# p2d-001.net
KiCad netlist of a schematic drawn in EAGLE
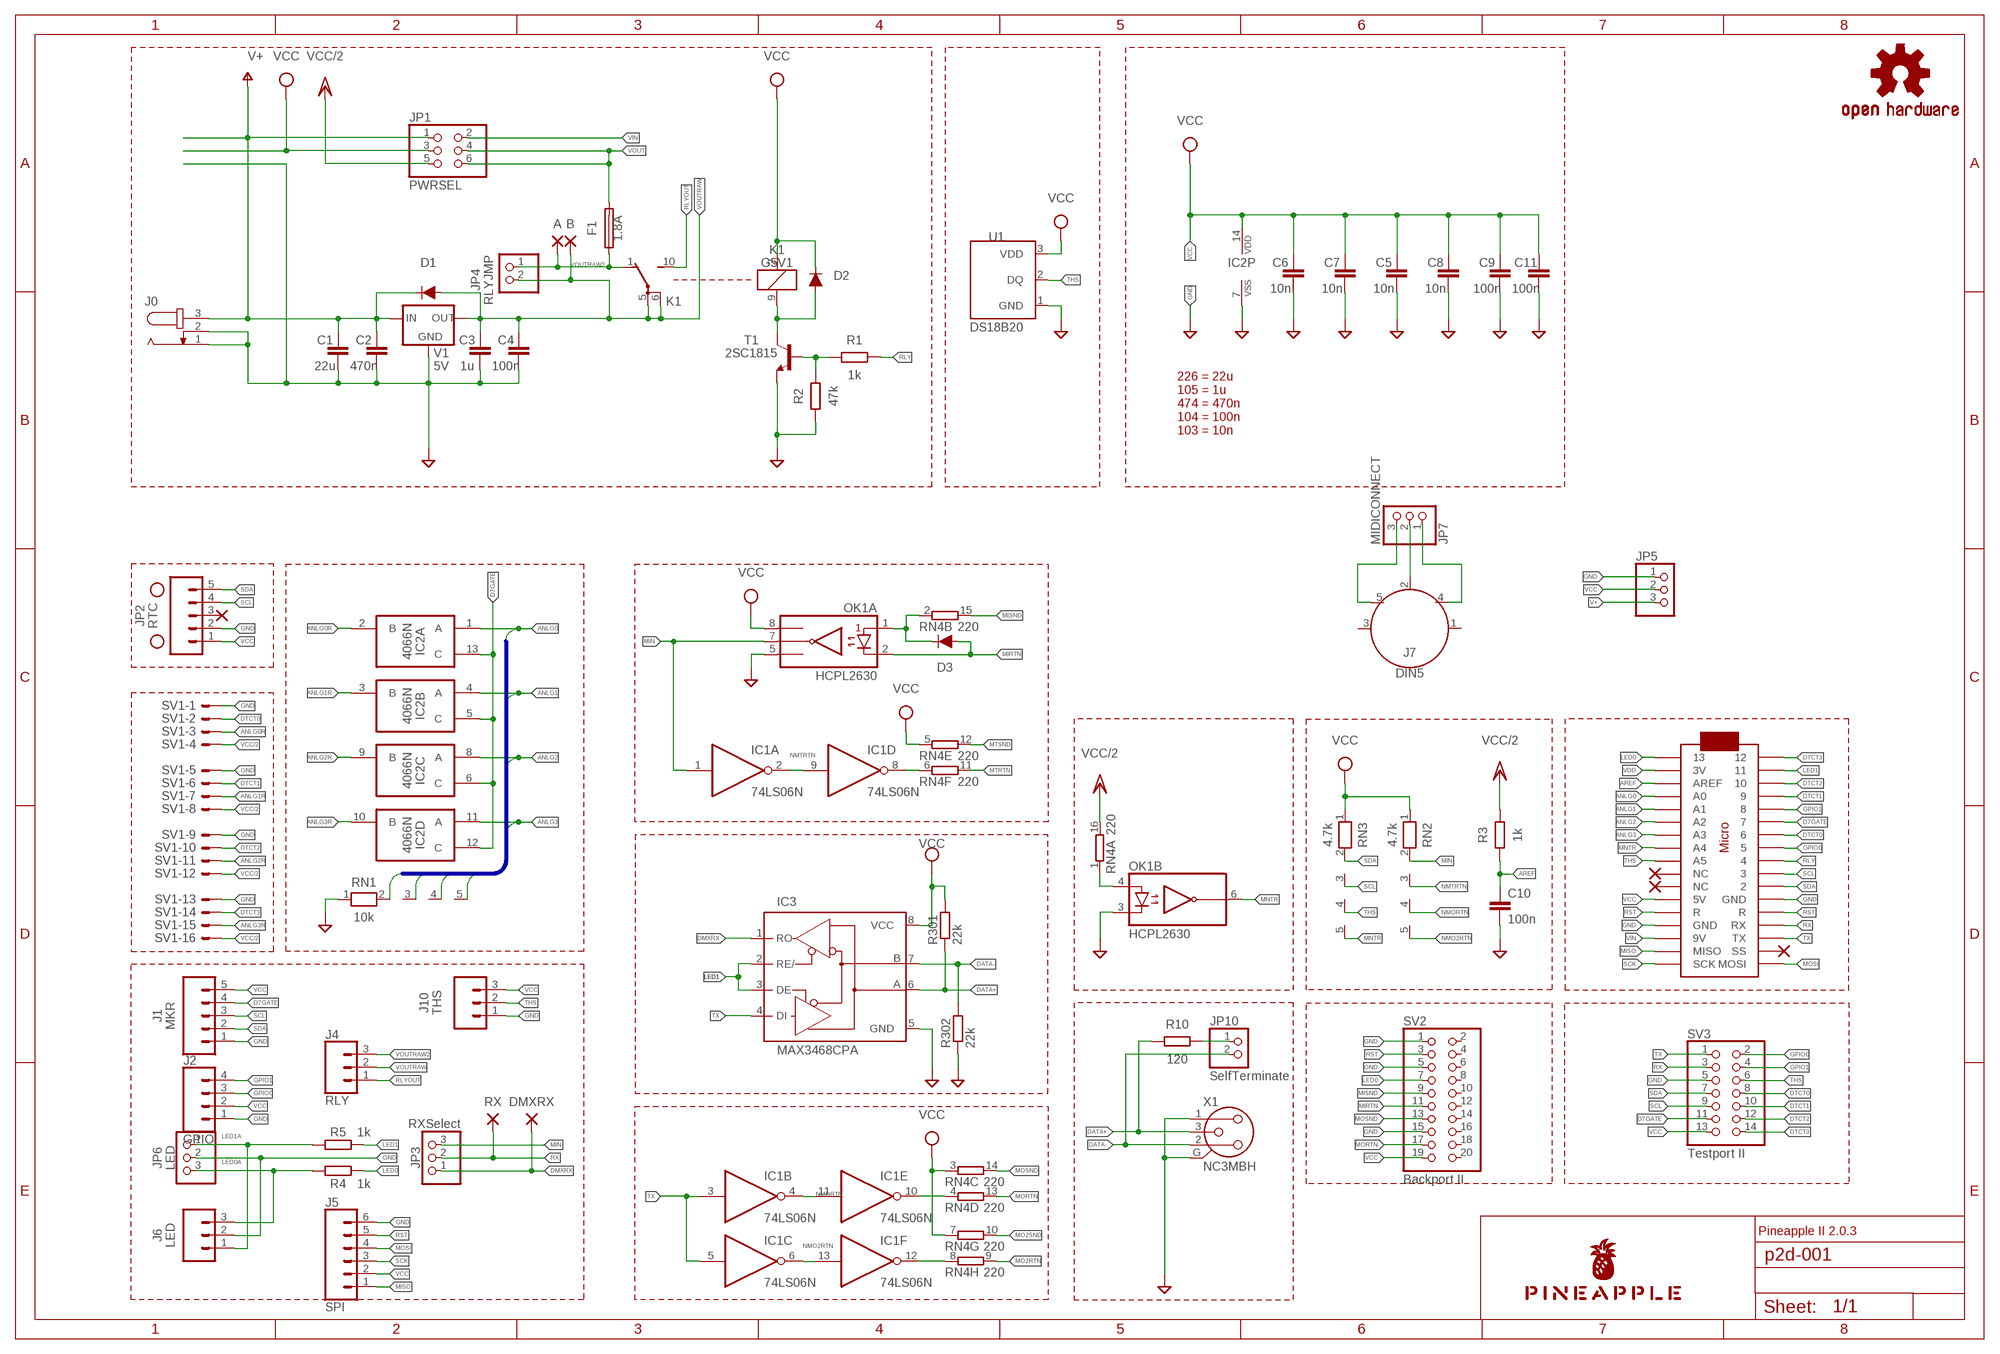
[diagram p0: schematic, sheet 1]

(export (version "E")
  (design (tool "Eeschema 10.0.6"))
  (components
    (comp (ref "A")
      (value "SMD2")
      (footprint "eagle-import:SMD1,27-2,54")
      (libsource (lib "eagle-import") (part "SMD2"))
    )
    (comp (ref "B")
      (value "SMD2")
      (footprint "eagle-import:SMD1,27-2,54")
      (libsource (lib "eagle-import") (part "SMD2"))
    )
    (comp (ref "C1")
      (value "22u")
      (footprint "eagle-import:C025-050X050")
      (libsource (lib "eagle-import") (part "C-EU025-050X050"))
    )
    (comp (ref "C2")
      (value "470n")
      (footprint "eagle-import:C050-024X044")
      (libsource (lib "eagle-import") (part "C-EU050-024X044"))
    )
    (comp (ref "C3")
      (value "1u")
      (footprint "eagle-import:C050-024X044")
      (libsource (lib "eagle-import") (part "C-EU050-024X044"))
    )
    (comp (ref "C4")
      (value "100n")
      (footprint "eagle-import:C025-024X044")
      (libsource (lib "eagle-import") (part "C-EU025-024X044"))
    )
    (comp (ref "C5")
      (value "10n")
      (footprint "eagle-import:C025-024X044")
      (libsource (lib "eagle-import") (part "resistor_348_C-EU025-024X044"))
    )
    (comp (ref "C6")
      (value "10n")
      (footprint "eagle-import:C025-024X044")
      (libsource (lib "eagle-import") (part "resistor_348_C-EU025-024X044"))
    )
    (comp (ref "C7")
      (value "10n")
      (footprint "eagle-import:C025-024X044")
      (libsource (lib "eagle-import") (part "resistor_348_C-EU025-024X044"))
    )
    (comp (ref "C8")
      (value "10n")
      (footprint "eagle-import:C025-024X044")
      (libsource (lib "eagle-import") (part "resistor_348_C-EU025-024X044"))
    )
    (comp (ref "C9")
      (value "100n")
      (footprint "eagle-import:C025-024X044")
      (libsource (lib "eagle-import") (part "resistor_348_C-EU025-024X044"))
    )
    (comp (ref "C10")
      (value "100n")
      (footprint "eagle-import:C025-024X044")
      (libsource (lib "eagle-import") (part "C-EU025-024X044"))
    )
    (comp (ref "C11")
      (value "100n")
      (footprint "eagle-import:C025-024X044")
      (libsource (lib "eagle-import") (part "resistor_348_C-EU025-024X044"))
    )
    (comp (ref "D1")
      (value "DIODE-1N4148")
      (footprint "eagle-import:DIODE-1N4148")
      (libsource (lib "eagle-import") (part "DIODE-1N4148"))
    )
    (comp (ref "D2")
      (value "DIODE-1N4148")
      (footprint "eagle-import:DIODE-1N4148")
      (libsource (lib "eagle-import") (part "DIODE-1N4148"))
    )
    (comp (ref "D3")
      (value "DIODE-1N4148")
      (footprint "eagle-import:DIODE-1N4148")
      (libsource (lib "eagle-import") (part "DIODE-1N4148"))
    )
    (comp (ref "DMXRX")
      (value "SMD2")
      (footprint "eagle-import:SMD1,27-2,54")
      (libsource (lib "eagle-import") (part "SMD2"))
    )
    (comp (ref "F1")
      (value "1.8A")
      (footprint "eagle-import:TE5")
      (libsource (lib "eagle-import") (part "TE5"))
    )
    (comp (ref "H1")
      (value "STAND-OFF")
      (footprint "eagle-import:STAND-OFF")
      (libsource (lib "eagle-import") (part "STAND-OFF"))
    )
    (comp (ref "H2")
      (value "STAND-OFF")
      (footprint "eagle-import:STAND-OFF")
      (libsource (lib "eagle-import") (part "STAND-OFF"))
    )
    (comp (ref "IC1")
      (value "74LS06N")
      (footprint "eagle-import:DIL14")
      (libsource (lib "eagle-import") (part "7406NLS"))
    )
    (comp (ref "IC2")
      (value "4066N")
      (footprint "eagle-import:DIL14")
      (libsource (lib "eagle-import") (part "4066N"))
    )
    (comp (ref "IC3")
      (value "MAX3468CPA")
      (footprint "eagle-import:DIL08")
      (libsource (lib "eagle-import") (part "MAX34PA68C"))
    )
    (comp (ref "J0")
      (value "JACK-PLUG0")
      (footprint "eagle-import:SPC4077")
      (libsource (lib "eagle-import") (part "JACK-PLUG0"))
    )
    (comp (ref "J1")
      (value "MKR")
      (footprint "eagle-import:JST-5-PTH")
      (libsource (lib "eagle-import") (part "CONN_05JST"))
    )
    (comp (ref "J2")
      (value "GPIO")
      (footprint "eagle-import:JST-4-PTH")
      (libsource (lib "eagle-import") (part "CONN_04JST-PTH"))
    )
    (comp (ref "J4")
      (value "RLY")
      (footprint "eagle-import:JST-3-PTH-NS")
      (libsource (lib "eagle-import") (part "CONN_03JST-PTH-NS"))
    )
    (comp (ref "J5")
      (value "SPI")
      (footprint "eagle-import:1X06_1.27MM")
      (libsource (lib "eagle-import") (part "CONN_061.27MM"))
    )
    (comp (ref "J6")
      (value "LED")
      (footprint "eagle-import:JST-3-PTH-VERT")
      (libsource (lib "eagle-import") (part "CONN_03JST-PTH-VERT"))
    )
    (comp (ref "J7")
      (value "DIN5")
      (footprint "eagle-import:DIN5-RA-PTH")
      (libsource (lib "eagle-import") (part "DIN5"))
    )
    (comp (ref "J10")
      (value "THS")
      (footprint "eagle-import:JST-3-PTH")
      (libsource (lib "eagle-import") (part "CONN_03JST-PTH"))
    )
    (comp (ref "JP1")
      (value "PWRSEL")
      (footprint "eagle-import:2X03")
      (libsource (lib "eagle-import") (part "PINHD-2X3"))
    )
    (comp (ref "JP2")
      (value "RTC")
      (footprint "eagle-import:1X05")
      (libsource (lib "eagle-import") (part "CONN_05"))
    )
    (comp (ref "JP3")
      (value "RXSelect")
      (footprint "eagle-import:1X03")
      (libsource (lib "eagle-import") (part "PINHD-1X3"))
    )
    (comp (ref "JP4")
      (value "RLYJMP")
      (footprint "eagle-import:1X02")
      (libsource (lib "eagle-import") (part "PINHD-1X2"))
    )
    (comp (ref "JP5")
      (value "PINHD-1X3")
      (footprint "eagle-import:1X03")
      (libsource (lib "eagle-import") (part "PINHD-1X3"))
    )
    (comp (ref "JP6")
      (value "LED")
      (footprint "eagle-import:1X03")
      (libsource (lib "eagle-import") (part "PINHD-1X3"))
    )
    (comp (ref "JP7")
      (value "MIDICONNECT")
      (footprint "eagle-import:1X03")
      (libsource (lib "eagle-import") (part "PINHD-1X3"))
    )
    (comp (ref "JP10")
      (value "SelfTerminate")
      (footprint "eagle-import:1X02")
      (libsource (lib "eagle-import") (part "PINHD-1X2"))
    )
    (comp (ref "K1")
      (value "G5V1")
      (footprint "eagle-import:G5V1")
      (fields (field (name "MPN") "G5V-1-DC24"))
      (libsource (lib "eagle-import") (part "G5V1"))
    )
    (comp (ref "LOGO1")
      (value "OSHW-LOGOS-COPPER")
      (footprint "eagle-import:OSHW-LOGO-S_COPPER")
      (libsource (lib "eagle-import") (part "OSHW-LOGOS-COPPER"))
    )
    (comp (ref "MC1")
      (value "ARDUINOMICRO")
      (footprint "eagle-import:ARDUINOMICRO")
      (libsource (lib "eagle-import") (part "ARDUINOMICRO"))
    )
    (comp (ref "OK1")
      (value "HCPL2630")
      (footprint "eagle-import:DIL08")
      (fields (field (name "MF") "AGILENT TECHNOLOGIES") (field (name "MPN") "HCPL-2630-000E"))
      (libsource (lib "eagle-import") (part "HCPL2630"))
    )
    (comp (ref "R1")
      (value "1k")
      (footprint "eagle-import:0204_5")
      (libsource (lib "eagle-import") (part "resistor_348_R-EU_0204/5"))
    )
    (comp (ref "R2")
      (value "47k")
      (footprint "eagle-import:0204_5")
      (libsource (lib "eagle-import") (part "resistor_348_R-EU_0204/5"))
    )
    (comp (ref "R3")
      (value "1k")
      (footprint "eagle-import:0204_5")
      (libsource (lib "eagle-import") (part "resistor_348_R-EU_0204/5"))
    )
    (comp (ref "R4")
      (value "1k")
      (footprint "eagle-import:0204_5")
      (libsource (lib "eagle-import") (part "resistor_348_R-EU_0204/5"))
    )
    (comp (ref "R5")
      (value "1k")
      (footprint "eagle-import:0204_5")
      (libsource (lib "eagle-import") (part "resistor_348_R-EU_0204/5"))
    )
    (comp (ref "R10")
      (value "120")
      (footprint "eagle-import:0204_5")
      (libsource (lib "eagle-import") (part "resistor_348_R-EU_0204/5"))
    )
    (comp (ref "R301")
      (value "22k")
      (footprint "eagle-import:M2012")
      (libsource (lib "eagle-import") (part "R-EU_M2012"))
    )
    (comp (ref "R302")
      (value "22k")
      (footprint "eagle-import:M2012")
      (libsource (lib "eagle-import") (part "R-EU_M2012"))
    )
    (comp (ref "RN1")
      (value "10k")
      (footprint "eagle-import:RN-5")
      (libsource (lib "eagle-import") (part "RN04"))
    )
    (comp (ref "RN2")
      (value "4.7k")
      (footprint "eagle-import:RN-5")
      (libsource (lib "eagle-import") (part "RN04"))
    )
    (comp (ref "RN3")
      (value "4.7k")
      (footprint "eagle-import:RN-5")
      (libsource (lib "eagle-import") (part "RN04"))
    )
    (comp (ref "RN4")
      (value "220")
      (footprint "eagle-import:DIL16")
      (libsource (lib "eagle-import") (part "8R-N"))
    )
    (comp (ref "RX")
      (value "SMD2")
      (footprint "eagle-import:SMD1,27-2,54")
      (libsource (lib "eagle-import") (part "SMD2"))
    )
    (comp (ref "SV1")
      (value "ML16LE")
      (footprint "eagle-import:ML16L")
      (libsource (lib "eagle-import") (part "ML16LE"))
    )
    (comp (ref "SV2")
      (value "Backport II")
      (footprint "eagle-import:2X10")
      (libsource (lib "eagle-import") (part "PINHD-2X10"))
    )
    (comp (ref "SV3")
      (value "Testport II")
      (footprint "eagle-import:2X07")
      (libsource (lib "eagle-import") (part "PINHD-2X7"))
    )
    (comp (ref "T1")
      (value "2SC1815")
      (footprint "eagle-import:TO92-ECB")
      (libsource (lib "eagle-import") (part "2SC1815"))
    )
    (comp (ref "U$1")
      (value "PINEAPPLE450_SILK")
      (footprint "eagle-import:PINEAPPLE450_SILK")
      (libsource (lib "eagle-import") (part "PINEAPPLE450_SILK"))
    )
    (comp (ref "U1")
      (value "DS18B20")
      (footprint "eagle-import:TO-92-AMMO")
      (libsource (lib "eagle-import") (part "DS18B20"))
    )
    (comp (ref "V1")
      (value "5V")
      (footprint "eagle-import:78XXL")
      (libsource (lib "eagle-import") (part "78XXL"))
    )
    (comp (ref "X1")
      (value "NC3MBH")
      (footprint "eagle-import:NC3MBH")
      (fields (field (name "MF") "NEUTRIK"))
      (libsource (lib "eagle-import") (part "NC3MBH"))
    )
  )
  (nets
    (net (code "1") (name "/LED0A") (class "Default")
      (node (ref "J6") (pin "3") (pinfunction "3_3") (pintype "passive"))
      (node (ref "JP6") (pin "3") (pinfunction "3_3") (pintype "passive"))
      (node (ref "R4") (pin "1") (pinfunction "1_1") (pintype "passive"))
    )
    (net (code "2") (name "/LED1A") (class "Default")
      (node (ref "J6") (pin "1") (pinfunction "1_1") (pintype "passive"))
      (node (ref "JP6") (pin "1") (pinfunction "1_1") (pintype "passive"))
      (node (ref "R5") (pin "1") (pinfunction "1_1") (pintype "passive"))
    )
    (net (code "3") (name "ANLG0") (class "Default")
      (node (ref "IC2") (pin "1") (pinfunction "A_1") (pintype "tri_state"))
      (node (ref "MC1") (pin "P$31") (pinfunction "A0_P$31") (pintype "bidirectional"))
      (node (ref "RN1") (pin "2") (pinfunction "2_2") (pintype "passive"))
    )
    (net (code "4") (name "ANLG0R") (class "Default")
      (node (ref "IC2") (pin "2") (pinfunction "B_2") (pintype "tri_state"))
      (node (ref "SV1") (pin "3") (pinfunction "S_3") (pintype "passive"))
    )
    (net (code "5") (name "ANLG1") (class "Default")
      (node (ref "IC2") (pin "4") (pinfunction "A_4") (pintype "tri_state"))
      (node (ref "MC1") (pin "P$30") (pinfunction "A1_P$30") (pintype "bidirectional"))
      (node (ref "RN1") (pin "3") (pinfunction "3_3") (pintype "passive"))
    )
    (net (code "6") (name "ANLG1R") (class "Default")
      (node (ref "IC2") (pin "3") (pinfunction "B_3") (pintype "tri_state"))
      (node (ref "SV1") (pin "7") (pinfunction "S_7") (pintype "passive"))
    )
    (net (code "7") (name "ANLG2") (class "Default")
      (node (ref "IC2") (pin "8") (pinfunction "A_8") (pintype "tri_state"))
      (node (ref "MC1") (pin "P$29") (pinfunction "A2_P$29") (pintype "bidirectional"))
      (node (ref "RN1") (pin "4") (pinfunction "4_4") (pintype "passive"))
    )
    (net (code "8") (name "ANLG2R") (class "Default")
      (node (ref "IC2") (pin "9") (pinfunction "B_9") (pintype "tri_state"))
      (node (ref "SV1") (pin "11") (pinfunction "S_11") (pintype "passive"))
    )
    (net (code "9") (name "ANLG3") (class "Default")
      (node (ref "IC2") (pin "11") (pinfunction "A_11") (pintype "tri_state"))
      (node (ref "MC1") (pin "P$28") (pinfunction "A3_P$28") (pintype "bidirectional"))
      (node (ref "RN1") (pin "5") (pinfunction "5_5") (pintype "passive"))
    )
    (net (code "10") (name "ANLG3R") (class "Default")
      (node (ref "IC2") (pin "10") (pinfunction "B_10") (pintype "tri_state"))
      (node (ref "SV1") (pin "15") (pinfunction "S_15") (pintype "passive"))
    )
    (net (code "11") (name "AREF") (class "Default")
      (node (ref "C10") (pin "1") (pinfunction "1_1") (pintype "passive"))
      (node (ref "MC1") (pin "P$32") (pinfunction "AREF_P$32") (pintype "bidirectional"))
      (node (ref "R3") (pin "1") (pinfunction "1_1") (pintype "passive"))
    )
    (net (code "12") (name "D7GATE") (class "Default")
      (node (ref "IC2") (pin "12") (pinfunction "C_12") (pintype "input"))
      (node (ref "IC2") (pin "13") (pinfunction "C_13") (pintype "input"))
      (node (ref "IC2") (pin "5") (pinfunction "C_5") (pintype "input"))
      (node (ref "IC2") (pin "6") (pinfunction "C_6") (pintype "input"))
      (node (ref "J1") (pin "4") (pinfunction "4_4") (pintype "passive"))
      (node (ref "MC1") (pin "P$6") (pinfunction "7_P$6") (pintype "bidirectional"))
      (node (ref "SV3") (pin "11") (pinfunction "11_11") (pintype "passive"))
    )
    (net (code "13") (name "DATA+") (class "Default")
      (node (ref "IC3") (pin "6") (pinfunction "A_6") (pintype "passive"))
      (node (ref "R10") (pin "1") (pinfunction "1_1") (pintype "passive"))
      (node (ref "R301") (pin "1") (pinfunction "1_1") (pintype "passive"))
      (node (ref "X1") (pin "3") (pinfunction "3_3") (pintype "passive"))
    )
    (net (code "14") (name "DATA-") (class "Default")
      (node (ref "IC3") (pin "7") (pinfunction "B_7") (pintype "passive"))
      (node (ref "JP10") (pin "2") (pinfunction "2_2") (pintype "passive"))
      (node (ref "R302") (pin "2") (pinfunction "2_2") (pintype "passive"))
      (node (ref "X1") (pin "2") (pinfunction "2_2") (pintype "passive"))
    )
    (net (code "15") (name "DMXRX") (class "Default")
      (node (ref "DMXRX") (pin "1") (pinfunction "P_1") (pintype "passive"))
      (node (ref "IC3") (pin "1") (pinfunction "RO_1") (pintype "output"))
      (node (ref "JP3") (pin "1") (pinfunction "1_1") (pintype "passive"))
    )
    (net (code "16") (name "DTCT0") (class "Default")
      (node (ref "MC1") (pin "P$7") (pinfunction "6_P$7") (pintype "bidirectional"))
      (node (ref "SV1") (pin "2") (pinfunction "S_2") (pintype "passive"))
      (node (ref "SV3") (pin "8") (pinfunction "8_8") (pintype "passive"))
    )
    (net (code "17") (name "DTCT1") (class "Default")
      (node (ref "MC1") (pin "P$4") (pinfunction "9_P$4") (pintype "bidirectional"))
      (node (ref "SV1") (pin "6") (pinfunction "S_6") (pintype "passive"))
      (node (ref "SV3") (pin "10") (pinfunction "10_10") (pintype "passive"))
    )
    (net (code "18") (name "DTCT2") (class "Default")
      (node (ref "MC1") (pin "P$3") (pinfunction "10_P$3") (pintype "bidirectional"))
      (node (ref "SV1") (pin "10") (pinfunction "S_10") (pintype "passive"))
      (node (ref "SV3") (pin "12") (pinfunction "12_12") (pintype "passive"))
    )
    (net (code "19") (name "DTCT3") (class "Default")
      (node (ref "MC1") (pin "P$1") (pinfunction "12_P$1") (pintype "bidirectional"))
      (node (ref "SV1") (pin "14") (pinfunction "S_14") (pintype "passive"))
      (node (ref "SV3") (pin "14") (pinfunction "14_14") (pintype "passive"))
    )
    (net (code "20") (name "GND") (class "Default")
      (node (ref "C1") (pin "2") (pinfunction "2_2") (pintype "passive"))
      (node (ref "C10") (pin "2") (pinfunction "2_2") (pintype "passive"))
      (node (ref "C11") (pin "2") (pinfunction "2_2") (pintype "passive"))
      (node (ref "C2") (pin "2") (pinfunction "2_2") (pintype "passive"))
      (node (ref "C3") (pin "2") (pinfunction "2_2") (pintype "passive"))
      (node (ref "C4") (pin "2") (pinfunction "2_2") (pintype "passive"))
      (node (ref "C5") (pin "2") (pinfunction "2_2") (pintype "passive"))
      (node (ref "C6") (pin "2") (pinfunction "2_2") (pintype "passive"))
      (node (ref "C7") (pin "2") (pinfunction "2_2") (pintype "passive"))
      (node (ref "C8") (pin "2") (pinfunction "2_2") (pintype "passive"))
      (node (ref "C9") (pin "2") (pinfunction "2_2") (pintype "passive"))
      (node (ref "IC2") (pin "7") (pinfunction "VSS_7") (pintype "power_in"))
      (node (ref "IC3") (pin "5") (pinfunction "GND_5") (pintype "power_in"))
      (node (ref "J0") (pin "1") (pinfunction "1_1") (pintype "passive"))
      (node (ref "J0") (pin "2") (pinfunction "2_2") (pintype "passive"))
      (node (ref "J1") (pin "1") (pinfunction "1_1") (pintype "passive"))
      (node (ref "J10") (pin "1") (pinfunction "1_1") (pintype "passive"))
      (node (ref "J2") (pin "1") (pinfunction "1_1") (pintype "passive"))
      (node (ref "J5") (pin "6") (pinfunction "6_6") (pintype "passive"))
      (node (ref "J6") (pin "2") (pinfunction "2_2") (pintype "passive"))
      (node (ref "JP2") (pin "2") (pinfunction "2_2") (pintype "passive"))
      (node (ref "JP5") (pin "1") (pinfunction "1_1") (pintype "passive"))
      (node (ref "JP6") (pin "2") (pinfunction "2_2") (pintype "passive"))
      (node (ref "MC1") (pin "P$12") (pinfunction "GND_P$12") (pintype "bidirectional"))
      (node (ref "MC1") (pin "P$21") (pinfunction "GND_P$21") (pintype "bidirectional"))
      (node (ref "OK1") (pin "3") (pinfunction "C2_3") (pintype "passive"))
      (node (ref "OK1") (pin "5") (pinfunction "GND_5") (pintype "passive"))
      (node (ref "R2") (pin "1") (pinfunction "1_1") (pintype "passive"))
      (node (ref "R302") (pin "1") (pinfunction "1_1") (pintype "passive"))
      (node (ref "RN1") (pin "1") (pinfunction "1_1") (pintype "passive"))
      (node (ref "SV1") (pin "1") (pinfunction "S_1") (pintype "passive"))
      (node (ref "SV1") (pin "13") (pinfunction "S_13") (pintype "passive"))
      (node (ref "SV1") (pin "5") (pinfunction "S_5") (pintype "passive"))
      (node (ref "SV1") (pin "9") (pinfunction "S_9") (pintype "passive"))
      (node (ref "SV2") (pin "1") (pinfunction "1_1") (pintype "passive"))
      (node (ref "SV2") (pin "15") (pinfunction "15_15") (pintype "passive"))
      (node (ref "SV2") (pin "5") (pinfunction "5_5") (pintype "passive"))
      (node (ref "SV3") (pin "5") (pinfunction "5_5") (pintype "passive"))
      (node (ref "T1") (pin "E") (pinfunction "E_E") (pintype "passive"))
      (node (ref "U1") (pin "1") (pinfunction "GND_1") (pintype "power_in"))
      (node (ref "V1") (pin "GND") (pinfunction "GND_GND") (pintype "input"))
      (node (ref "X1") (pin "1") (pinfunction "1_1") (pintype "passive"))
      (node (ref "X1") (pin "G") (pinfunction "G_G") (pintype "passive"))
    )
    (net (code "21") (name "GPIO0") (class "Default")
      (node (ref "J2") (pin "3") (pinfunction "3_3") (pintype "passive"))
      (node (ref "MC1") (pin "P$8") (pinfunction "5_P$8") (pintype "bidirectional"))
      (node (ref "SV3") (pin "2") (pinfunction "2_2") (pintype "passive"))
    )
    (net (code "22") (name "GPIO1") (class "Default")
      (node (ref "J2") (pin "4") (pinfunction "4_4") (pintype "passive"))
      (node (ref "MC1") (pin "P$5") (pinfunction "8_P$5") (pintype "bidirectional"))
      (node (ref "SV3") (pin "4") (pinfunction "4_4") (pintype "passive"))
    )
    (net (code "23") (name "LED0") (class "Default")
      (node (ref "MC1") (pin "P$34") (pinfunction "13_P$34") (pintype "bidirectional"))
      (node (ref "R4") (pin "2") (pinfunction "2_2") (pintype "passive"))
      (node (ref "SV2") (pin "7") (pinfunction "7_7") (pintype "passive"))
    )
    (net (code "24") (name "LED1") (class "Default")
      (node (ref "IC3") (pin "2") (pinfunction "RE/_2") (pintype "input"))
      (node (ref "IC3") (pin "3") (pinfunction "DE_3") (pintype "input"))
      (node (ref "MC1") (pin "P$2") (pinfunction "11_P$2") (pintype "bidirectional"))
      (node (ref "R5") (pin "2") (pinfunction "2_2") (pintype "passive"))
    )
    (net (code "25") (name "MIN") (class "Default")
      (node (ref "IC1") (pin "1") (pinfunction "I_1") (pintype "input"))
      (node (ref "JP3") (pin "3") (pinfunction "3_3") (pintype "passive"))
      (node (ref "OK1") (pin "7") (pinfunction "VO1_7") (pintype "passive"))
      (node (ref "RN2") (pin "2") (pinfunction "2_2") (pintype "passive"))
    )
    (net (code "26") (name "MIRTN") (class "Default")
      (node (ref "D3") (pin "A") (pinfunction "A_A") (pintype "passive"))
      (node (ref "OK1") (pin "2") (pinfunction "C1_2") (pintype "passive"))
      (node (ref "SV2") (pin "11") (pinfunction "11_11") (pintype "passive"))
    )
    (net (code "27") (name "MISND") (class "Default")
      (node (ref "RN4") (pin "15") (pinfunction "2_15") (pintype "passive"))
      (node (ref "SV2") (pin "9") (pinfunction "9_9") (pintype "passive"))
    )
    (net (code "28") (name "MISO") (class "Default")
      (node (ref "J5") (pin "1") (pinfunction "1_1") (pintype "passive"))
      (node (ref "MC1") (pin "P$19") (pinfunction "MISO_P$19") (pintype "bidirectional"))
    )
    (net (code "29") (name "MNTR") (class "Default")
      (node (ref "MC1") (pin "P$27") (pinfunction "A4_P$27") (pintype "bidirectional"))
      (node (ref "OK1") (pin "6") (pinfunction "VO2_6") (pintype "passive"))
      (node (ref "RN3") (pin "5") (pinfunction "5_5") (pintype "passive"))
    )
    (net (code "30") (name "MO2RTN") (class "Default")
      (node (ref "RN4") (pin "9") (pinfunction "2_9") (pintype "passive"))
    )
    (net (code "31") (name "MO2SND") (class "Default")
      (node (ref "RN4") (pin "10") (pinfunction "2_10") (pintype "passive"))
    )
    (net (code "32") (name "MORTN") (class "Default")
      (node (ref "RN4") (pin "13") (pinfunction "2_13") (pintype "passive"))
      (node (ref "SV2") (pin "17") (pinfunction "17_17") (pintype "passive"))
    )
    (net (code "33") (name "MOSI") (class "Default")
      (node (ref "J5") (pin "4") (pinfunction "4_4") (pintype "passive"))
      (node (ref "MC1") (pin "P$17") (pinfunction "MOSI_P$17") (pintype "bidirectional"))
    )
    (net (code "34") (name "MOSND") (class "Default")
      (node (ref "RN4") (pin "14") (pinfunction "2_14") (pintype "passive"))
      (node (ref "SV2") (pin "13") (pinfunction "13_13") (pintype "passive"))
    )
    (net (code "35") (name "MTRTN") (class "Default")
      (node (ref "RN4") (pin "11") (pinfunction "2_11") (pintype "passive"))
    )
    (net (code "36") (name "MTSND") (class "Default")
      (node (ref "RN4") (pin "12") (pinfunction "2_12") (pintype "passive"))
    )
    (net (code "37") (name "NMO2RTN") (class "Default")
      (node (ref "IC1") (pin "13") (pinfunction "I_13") (pintype "input"))
      (node (ref "IC1") (pin "6") (pinfunction "O_6") (pintype "open_collector"))
      (node (ref "RN2") (pin "5") (pinfunction "5_5") (pintype "passive"))
    )
    (net (code "38") (name "NMORTN") (class "Default")
      (node (ref "IC1") (pin "11") (pinfunction "I_11") (pintype "input"))
      (node (ref "IC1") (pin "4") (pinfunction "O_4") (pintype "open_collector"))
      (node (ref "RN2") (pin "4") (pinfunction "4_4") (pintype "passive"))
    )
    (net (code "39") (name "NMTRTN") (class "Default")
      (node (ref "IC1") (pin "2") (pinfunction "O_2") (pintype "open_collector"))
      (node (ref "IC1") (pin "9") (pinfunction "I_9") (pintype "input"))
      (node (ref "RN2") (pin "3") (pinfunction "3_3") (pintype "passive"))
    )
    (net (code "40") (name "Net-(IC1D-O)") (class "Default")
      (node (ref "IC1") (pin "8") (pinfunction "O_8") (pintype "open_collector"))
      (node (ref "RN4") (pin "6") (pinfunction "1_6") (pintype "passive"))
    )
    (net (code "41") (name "Net-(IC1E-O)") (class "Default")
      (node (ref "IC1") (pin "10") (pinfunction "O_10") (pintype "open_collector"))
      (node (ref "RN4") (pin "4") (pinfunction "1_4") (pintype "passive"))
    )
    (net (code "42") (name "Net-(IC1F-O)") (class "Default")
      (node (ref "IC1") (pin "12") (pinfunction "O_12") (pintype "open_collector"))
      (node (ref "RN4") (pin "8") (pinfunction "1_8") (pintype "passive"))
    )
    (net (code "43") (name "Net-(J7-Pad2)") (class "Default")
      (node (ref "J7") (pin "2") (pinfunction "2_2") (pintype "bidirectional"))
      (node (ref "JP7") (pin "2") (pinfunction "2_2") (pintype "passive"))
    )
    (net (code "44") (name "Net-(J7-Pad4)") (class "Default")
      (node (ref "J7") (pin "4") (pinfunction "4_4") (pintype "bidirectional"))
      (node (ref "JP7") (pin "1") (pinfunction "1_1") (pintype "passive"))
    )
    (net (code "45") (name "Net-(J7-Pad5)") (class "Default")
      (node (ref "J7") (pin "5") (pinfunction "5_5") (pintype "bidirectional"))
      (node (ref "JP7") (pin "3") (pinfunction "3_3") (pintype "passive"))
    )
    (net (code "46") (name "Net-(JP10-Pad1)") (class "Default")
      (node (ref "JP10") (pin "1") (pinfunction "1_1") (pintype "passive"))
      (node (ref "R10") (pin "2") (pinfunction "2_2") (pintype "passive"))
    )
    (net (code "47") (name "Net-(K1A-2)") (class "Default")
      (node (ref "D2") (pin "A") (pinfunction "A_A") (pintype "passive"))
      (node (ref "K1") (pin "9") (pinfunction "2_9") (pintype "passive"))
      (node (ref "T1") (pin "C") (pinfunction "C_C") (pintype "passive"))
    )
    (net (code "48") (name "Net-(OK1A-A1)") (class "Default")
      (node (ref "D3") (pin "C") (pinfunction "C_C") (pintype "passive"))
      (node (ref "OK1") (pin "1") (pinfunction "A1_1") (pintype "passive"))
      (node (ref "RN4") (pin "2") (pinfunction "1_2") (pintype "passive"))
    )
    (net (code "49") (name "Net-(OK1B-A2)") (class "Default")
      (node (ref "OK1") (pin "4") (pinfunction "A2_4") (pintype "passive"))
      (node (ref "RN4") (pin "1") (pinfunction "1_1") (pintype "passive"))
    )
    (net (code "50") (name "Net-(R1-Pad1)") (class "Default")
      (node (ref "R1") (pin "1") (pinfunction "1_1") (pintype "passive"))
      (node (ref "R2") (pin "2") (pinfunction "2_2") (pintype "passive"))
      (node (ref "T1") (pin "B") (pinfunction "B_B") (pintype "passive"))
    )
    (net (code "51") (name "RLY") (class "Default")
      (node (ref "MC1") (pin "P$9") (pinfunction "4_P$9") (pintype "bidirectional"))
      (node (ref "R1") (pin "2") (pinfunction "2_2") (pintype "passive"))
    )
    (net (code "52") (name "RLYOUT") (class "Default")
      (node (ref "J4") (pin "1") (pinfunction "1_1") (pintype "passive"))
      (node (ref "K1") (pin "10") (pinfunction "S_10") (pintype "passive"))
    )
    (net (code "53") (name "RST") (class "Default")
      (node (ref "J5") (pin "5") (pinfunction "5_5") (pintype "passive"))
      (node (ref "MC1") (pin "P$13") (pinfunction "R_P$13") (pintype "bidirectional"))
      (node (ref "MC1") (pin "P$22") (pinfunction "R_P$22") (pintype "bidirectional"))
      (node (ref "SV2") (pin "3") (pinfunction "3_3") (pintype "passive"))
    )
    (net (code "54") (name "RX") (class "Default")
      (node (ref "JP3") (pin "2") (pinfunction "2_2") (pintype "passive"))
      (node (ref "MC1") (pin "P$14") (pinfunction "RX_P$14") (pintype "bidirectional"))
      (node (ref "RX") (pin "1") (pinfunction "P_1") (pintype "passive"))
      (node (ref "SV3") (pin "3") (pinfunction "3_3") (pintype "passive"))
    )
    (net (code "55") (name "SCK") (class "Default")
      (node (ref "J5") (pin "3") (pinfunction "3_3") (pintype "passive"))
      (node (ref "MC1") (pin "P$18") (pinfunction "SCK_P$18") (pintype "bidirectional"))
    )
    (net (code "56") (name "SCL") (class "Default")
      (node (ref "J1") (pin "3") (pinfunction "3_3") (pintype "passive"))
      (node (ref "JP2") (pin "4") (pinfunction "4_4") (pintype "passive"))
      (node (ref "MC1") (pin "P$10") (pinfunction "3_P$10") (pintype "bidirectional"))
      (node (ref "RN3") (pin "3") (pinfunction "3_3") (pintype "passive"))
      (node (ref "SV3") (pin "9") (pinfunction "9_9") (pintype "passive"))
    )
    (net (code "57") (name "SDA") (class "Default")
      (node (ref "J1") (pin "2") (pinfunction "2_2") (pintype "passive"))
      (node (ref "JP2") (pin "5") (pinfunction "5_5") (pintype "passive"))
      (node (ref "MC1") (pin "P$11") (pinfunction "2_P$11") (pintype "bidirectional"))
      (node (ref "RN3") (pin "2") (pinfunction "2_2") (pintype "passive"))
      (node (ref "SV3") (pin "7") (pinfunction "7_7") (pintype "passive"))
    )
    (net (code "58") (name "THS") (class "Default")
      (node (ref "J10") (pin "2") (pinfunction "2_2") (pintype "passive"))
      (node (ref "MC1") (pin "P$26") (pinfunction "A5_P$26") (pintype "bidirectional"))
      (node (ref "RN3") (pin "4") (pinfunction "4_4") (pintype "passive"))
      (node (ref "SV3") (pin "6") (pinfunction "6_6") (pintype "passive"))
      (node (ref "U1") (pin "2") (pinfunction "DQ_2") (pintype "bidirectional"))
    )
    (net (code "59") (name "TX") (class "Default")
      (node (ref "IC1") (pin "3") (pinfunction "I_3") (pintype "input"))
      (node (ref "IC1") (pin "5") (pinfunction "I_5") (pintype "input"))
      (node (ref "IC3") (pin "4") (pinfunction "DI_4") (pintype "input"))
      (node (ref "MC1") (pin "P$15") (pinfunction "TX_P$15") (pintype "bidirectional"))
      (node (ref "SV3") (pin "1") (pinfunction "1_1") (pintype "passive"))
    )
    (net (code "60") (name "V+") (class "Default")
      (node (ref "C1") (pin "1") (pinfunction "1_1") (pintype "passive"))
      (node (ref "C2") (pin "1") (pinfunction "1_1") (pintype "passive"))
      (node (ref "D1") (pin "C") (pinfunction "C_C") (pintype "passive"))
      (node (ref "J0") (pin "3") (pinfunction "3_3") (pintype "passive"))
      (node (ref "JP1") (pin "1") (pinfunction "1_1") (pintype "passive"))
      (node (ref "JP5") (pin "3") (pinfunction "3_3") (pintype "passive"))
      (node (ref "V1") (pin "IN") (pinfunction "IN_IN") (pintype "input"))
    )
    (net (code "61") (name "VCC") (class "Default")
      (node (ref "C11") (pin "1") (pinfunction "1_1") (pintype "passive"))
      (node (ref "C5") (pin "1") (pinfunction "1_1") (pintype "passive"))
      (node (ref "C6") (pin "1") (pinfunction "1_1") (pintype "passive"))
      (node (ref "C7") (pin "1") (pinfunction "1_1") (pintype "passive"))
      (node (ref "C8") (pin "1") (pinfunction "1_1") (pintype "passive"))
      (node (ref "C9") (pin "1") (pinfunction "1_1") (pintype "passive"))
      (node (ref "D2") (pin "C") (pinfunction "C_C") (pintype "passive"))
      (node (ref "IC2") (pin "14") (pinfunction "VDD_14") (pintype "power_in"))
      (node (ref "IC3") (pin "8") (pinfunction "VCC_8") (pintype "power_in"))
      (node (ref "J1") (pin "5") (pinfunction "5_5") (pintype "passive"))
      (node (ref "J10") (pin "3") (pinfunction "3_3") (pintype "passive"))
      (node (ref "J2") (pin "2") (pinfunction "2_2") (pintype "passive"))
      (node (ref "J5") (pin "2") (pinfunction "2_2") (pintype "passive"))
      (node (ref "JP1") (pin "3") (pinfunction "3_3") (pintype "passive"))
      (node (ref "JP2") (pin "1") (pinfunction "1_1") (pintype "passive"))
      (node (ref "JP5") (pin "2") (pinfunction "2_2") (pintype "passive"))
      (node (ref "K1") (pin "2") (pinfunction "1_2") (pintype "passive"))
      (node (ref "MC1") (pin "P$23") (pinfunction "5V_P$23") (pintype "bidirectional"))
      (node (ref "OK1") (pin "8") (pinfunction "VCC_8") (pintype "passive"))
      (node (ref "R301") (pin "2") (pinfunction "2_2") (pintype "passive"))
      (node (ref "RN2") (pin "1") (pinfunction "1_1") (pintype "passive"))
      (node (ref "RN3") (pin "1") (pinfunction "1_1") (pintype "passive"))
      (node (ref "RN4") (pin "3") (pinfunction "1_3") (pintype "passive"))
      (node (ref "RN4") (pin "5") (pinfunction "1_5") (pintype "passive"))
      (node (ref "RN4") (pin "7") (pinfunction "1_7") (pintype "passive"))
      (node (ref "SV2") (pin "19") (pinfunction "19_19") (pintype "passive"))
      (node (ref "SV3") (pin "13") (pinfunction "13_13") (pintype "passive"))
      (node (ref "U1") (pin "3") (pinfunction "VDD_3") (pintype "power_in"))
    )
    (net (code "62") (name "VCC{slash}2") (class "Default")
      (node (ref "JP1") (pin "5") (pinfunction "5_5") (pintype "passive"))
      (node (ref "R3") (pin "2") (pinfunction "2_2") (pintype "passive"))
      (node (ref "RN4") (pin "16") (pinfunction "2_16") (pintype "passive"))
      (node (ref "SV1") (pin "12") (pinfunction "S_12") (pintype "passive"))
      (node (ref "SV1") (pin "16") (pinfunction "S_16") (pintype "passive"))
      (node (ref "SV1") (pin "4") (pinfunction "S_4") (pintype "passive"))
      (node (ref "SV1") (pin "8") (pinfunction "S_8") (pintype "passive"))
    )
    (net (code "63") (name "VDD") (class "Default")
      (node (ref "MC1") (pin "P$33") (pinfunction "3V_P$33") (pintype "bidirectional"))
    )
    (net (code "64") (name "VIN") (class "Default")
      (node (ref "JP1") (pin "2") (pinfunction "2_2") (pintype "passive"))
      (node (ref "MC1") (pin "P$20") (pinfunction "9V_P$20") (pintype "bidirectional"))
    )
    (net (code "65") (name "VOUT") (class "Default")
      (node (ref "F1") (pin "2") (pinfunction "2_2") (pintype "passive"))
      (node (ref "JP1") (pin "4") (pinfunction "4_4") (pintype "passive"))
      (node (ref "JP1") (pin "6") (pinfunction "6_6") (pintype "passive"))
    )
    (net (code "66") (name "VOUTRAW") (class "Default")
      (node (ref "B") (pin "1") (pinfunction "P_1") (pintype "passive"))
      (node (ref "C3") (pin "1") (pinfunction "1_1") (pintype "passive"))
      (node (ref "C4") (pin "1") (pinfunction "1_1") (pintype "passive"))
      (node (ref "D1") (pin "A") (pinfunction "A_A") (pintype "passive"))
      (node (ref "J4") (pin "2") (pinfunction "2_2") (pintype "passive"))
      (node (ref "JP4") (pin "2") (pinfunction "2_2") (pintype "passive"))
      (node (ref "K1") (pin "5") (pinfunction "P_5") (pintype "passive"))
      (node (ref "K1") (pin "6") (pinfunction "P_6") (pintype "passive"))
      (node (ref "V1") (pin "OUT") (pinfunction "OUT_OUT") (pintype "passive"))
    )
    (net (code "67") (name "VOUTRAW2") (class "Default")
      (node (ref "A") (pin "1") (pinfunction "P_1") (pintype "passive"))
      (node (ref "F1") (pin "1") (pinfunction "1_1") (pintype "passive"))
      (node (ref "J4") (pin "3") (pinfunction "3_3") (pintype "passive"))
      (node (ref "JP4") (pin "1") (pinfunction "1_1") (pintype "passive"))
      (node (ref "K1") (pin "1") (pinfunction "O_1") (pintype "passive"))
    )
    (net (code "68") (name "unconnected-(J7-Pad1)") (class "Default")
      (node (ref "J7") (pin "1") (pinfunction "1_1") (pintype "bidirectional"))
    )
    (net (code "69") (name "unconnected-(J7-Pad3)") (class "Default")
      (node (ref "J7") (pin "3") (pinfunction "3_3") (pintype "bidirectional"))
    )
    (net (code "70") (name "unconnected-(JP2-Pad3)") (class "Default")
      (node (ref "JP2") (pin "3") (pinfunction "3_3") (pintype "passive"))
    )
    (net (code "71") (name "unconnected-(MC1-NC-PadP$24)") (class "Default")
      (node (ref "MC1") (pin "P$24") (pinfunction "NC_P$24") (pintype "bidirectional"))
    )
    (net (code "72") (name "unconnected-(MC1-NC-PadP$25)") (class "Default")
      (node (ref "MC1") (pin "P$25") (pinfunction "NC_P$25") (pintype "bidirectional"))
    )
    (net (code "73") (name "unconnected-(MC1-SS-PadP$16)") (class "Default")
      (node (ref "MC1") (pin "P$16") (pinfunction "SS_P$16") (pintype "bidirectional"))
    )
    (net (code "74") (name "unconnected-(SV2-Pad2)") (class "Default")
      (node (ref "SV2") (pin "2") (pinfunction "2_2") (pintype "passive"))
    )
    (net (code "75") (name "unconnected-(SV2-Pad4)") (class "Default")
      (node (ref "SV2") (pin "4") (pinfunction "4_4") (pintype "passive"))
    )
    (net (code "76") (name "unconnected-(SV2-Pad6)") (class "Default")
      (node (ref "SV2") (pin "6") (pinfunction "6_6") (pintype "passive"))
    )
    (net (code "77") (name "unconnected-(SV2-Pad8)") (class "Default")
      (node (ref "SV2") (pin "8") (pinfunction "8_8") (pintype "passive"))
    )
    (net (code "78") (name "unconnected-(SV2-Pad10)") (class "Default")
      (node (ref "SV2") (pin "10") (pinfunction "10_10") (pintype "passive"))
    )
    (net (code "79") (name "unconnected-(SV2-Pad12)") (class "Default")
      (node (ref "SV2") (pin "12") (pinfunction "12_12") (pintype "passive"))
    )
    (net (code "80") (name "unconnected-(SV2-Pad14)") (class "Default")
      (node (ref "SV2") (pin "14") (pinfunction "14_14") (pintype "passive"))
    )
    (net (code "81") (name "unconnected-(SV2-Pad16)") (class "Default")
      (node (ref "SV2") (pin "16") (pinfunction "16_16") (pintype "passive"))
    )
    (net (code "82") (name "unconnected-(SV2-Pad18)") (class "Default")
      (node (ref "SV2") (pin "18") (pinfunction "18_18") (pintype "passive"))
    )
    (net (code "83") (name "unconnected-(SV2-Pad20)") (class "Default")
      (node (ref "SV2") (pin "20") (pinfunction "20_20") (pintype "passive"))
    )
  )
)
